# wah.net
KiCad netlist of a schematic drawn in Altium Designer
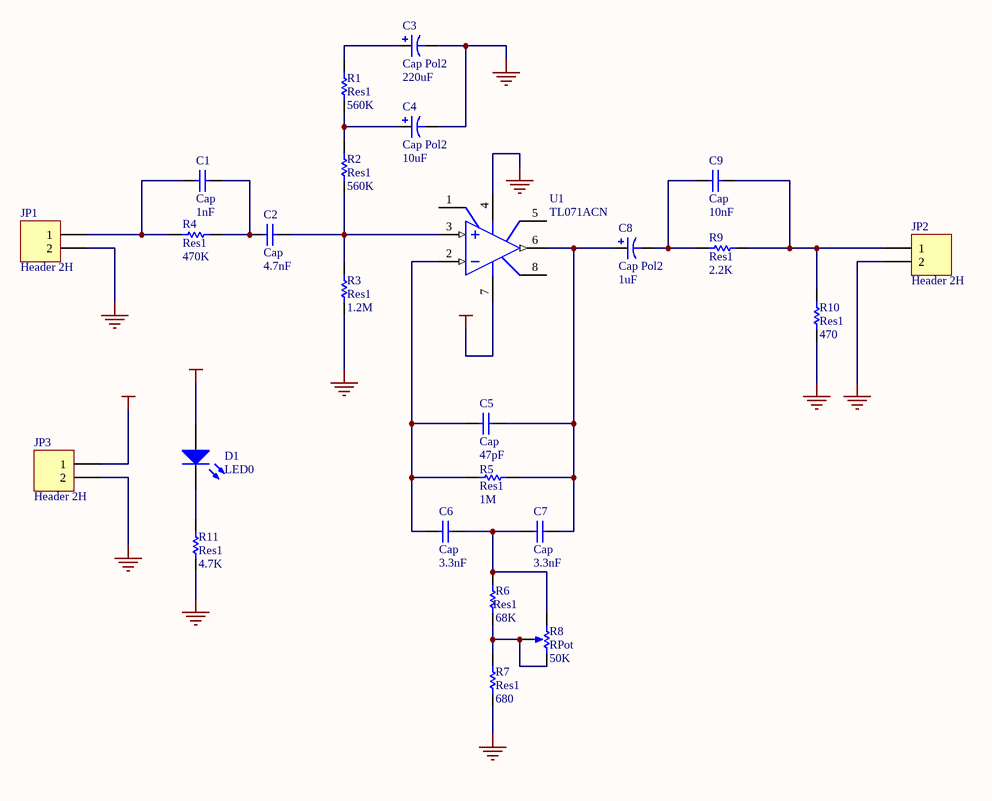
[diagram p0: wah.SCHDOC]

(export (version "E")
  (design (tool "Eeschema 10.0.6"))
  (components
    (comp (ref "C1")
      (value "Cap")
      (footprint "CAPR2.54-5.1X3.2")
      (description "Capacitor")
      (fields (field (name "ALTIUM_VALUE") "1nF") (field (name "PUBLISHER") "Altium Limited"))
      (libsource (lib "Miscellaneous Devices") (part "Cap"))
    )
    (comp (ref "C2")
      (value "Cap")
      (footprint "CAPR2.54-5.1X3.2")
      (description "Capacitor")
      (fields (field (name "ALTIUM_VALUE") "4.7nF") (field (name "PUBLISHER") "Altium Limited"))
      (libsource (lib "Miscellaneous Devices") (part "Cap"))
    )
    (comp (ref "C3")
      (value "Cap Pol2")
      (footprint "CAPPR2-5X6.8")
      (description "Polarized Capacitor (Axial)")
      (fields (field (name "ALTIUM_VALUE") "220uF") (field (name "PUBLISHER") "Altium Limited"))
      (libsource (lib "Miscellaneous Devices") (part "Cap Pol2"))
    )
    (comp (ref "C4")
      (value "Cap Pol2")
      (footprint "CAPPR2-5X6.8")
      (description "Polarized Capacitor (Axial)")
      (fields (field (name "ALTIUM_VALUE") "10uF") (field (name "PUBLISHER") "Altium Limited"))
      (libsource (lib "Miscellaneous Devices") (part "Cap Pol2"))
    )
    (comp (ref "C5")
      (value "Cap")
      (footprint "CAPR2.54-5.1X3.2")
      (description "Capacitor")
      (fields (field (name "ALTIUM_VALUE") "47pF") (field (name "PUBLISHER") "Altium Limited"))
      (libsource (lib "Miscellaneous Devices") (part "Cap"))
    )
    (comp (ref "C6")
      (value "Cap")
      (footprint "CAPR2.54-5.1X3.2")
      (description "Capacitor")
      (fields (field (name "ALTIUM_VALUE") "3.3nF") (field (name "PUBLISHER") "Altium Limited"))
      (libsource (lib "Miscellaneous Devices") (part "Cap"))
    )
    (comp (ref "C7")
      (value "Cap")
      (footprint "CAPR2.54-5.1X3.2")
      (description "Capacitor")
      (fields (field (name "ALTIUM_VALUE") "3.3nF") (field (name "PUBLISHER") "Altium Limited"))
      (libsource (lib "Miscellaneous Devices") (part "Cap"))
    )
    (comp (ref "C8")
      (value "Cap Pol2")
      (footprint "CAPPR2-5X6.8")
      (description "Polarized Capacitor (Axial)")
      (fields (field (name "ALTIUM_VALUE") "1uF") (field (name "PUBLISHER") "Altium Limited"))
      (libsource (lib "Miscellaneous Devices") (part "Cap Pol2"))
    )
    (comp (ref "C9")
      (value "Cap")
      (footprint "CAPR2.54-5.1X3.2")
      (description "Capacitor")
      (fields (field (name "ALTIUM_VALUE") "10nF") (field (name "PUBLISHER") "Altium Limited"))
      (libsource (lib "Miscellaneous Devices") (part "Cap"))
    )
    (comp (ref "D1")
      (value "LED0")
      (footprint "BAT-2")
      (description "Typical INFRARED GaAs LED")
      (fields (field (name "PUBLISHER") "Altium Limited"))
      (libsource (lib "Miscellaneous Devices") (part "LED0"))
    )
    (comp (ref "JP1")
      (value "Header 2H")
      (footprint "HDR1X2")
      (description "Header, 2-Pin, Right Angle")
      (fields (field (name "PUBLISHER") "Altium Limited"))
      (libsource (lib "") (part "Header 2H_1"))
    )
    (comp (ref "JP2")
      (value "Header 2H")
      (footprint "HDR1X2")
      (description "Header, 2-Pin, Right Angle")
      (fields (field (name "PUBLISHER") "Altium Limited"))
      (libsource (lib "Miscellaneous Connectors") (part "Header 2H"))
    )
    (comp (ref "JP3")
      (value "Header 2H")
      (footprint "HDR1X2")
      (description "Header, 2-Pin, Right Angle")
      (fields (field (name "PUBLISHER") "Altium Limited"))
      (libsource (lib "") (part "Header 2H_1"))
    )
    (comp (ref "R1")
      (value "Res1")
      (footprint "AXIAL-0.3")
      (description "Resistor")
      (fields (field (name "ALTIUM_VALUE") "560K") (field (name "PUBLISHER") "Altium Limited"))
      (libsource (lib "Miscellaneous Devices") (part "Res1"))
    )
    (comp (ref "R2")
      (value "Res1")
      (footprint "AXIAL-0.3")
      (description "Resistor")
      (fields (field (name "ALTIUM_VALUE") "560K") (field (name "PUBLISHER") "Altium Limited"))
      (libsource (lib "Miscellaneous Devices") (part "Res1"))
    )
    (comp (ref "R3")
      (value "Res1")
      (footprint "AXIAL-0.3")
      (description "Resistor")
      (fields (field (name "ALTIUM_VALUE") "1.2M") (field (name "PUBLISHER") "Altium Limited"))
      (libsource (lib "Miscellaneous Devices") (part "Res1"))
    )
    (comp (ref "R4")
      (value "Res1")
      (footprint "AXIAL-0.3")
      (description "Resistor")
      (fields (field (name "ALTIUM_VALUE") "470K") (field (name "PUBLISHER") "Altium Limited"))
      (libsource (lib "Miscellaneous Devices") (part "Res1"))
    )
    (comp (ref "R5")
      (value "Res1")
      (footprint "AXIAL-0.3")
      (description "Resistor")
      (fields (field (name "ALTIUM_VALUE") "1M") (field (name "PUBLISHER") "Altium Limited"))
      (libsource (lib "Miscellaneous Devices") (part "Res1"))
    )
    (comp (ref "R6")
      (value "Res1")
      (footprint "AXIAL-0.3")
      (description "Resistor")
      (fields (field (name "ALTIUM_VALUE") "68K") (field (name "PUBLISHER") "Altium Limited"))
      (libsource (lib "Miscellaneous Devices") (part "Res1"))
    )
    (comp (ref "R7")
      (value "Res1")
      (footprint "AXIAL-0.3")
      (description "Resistor")
      (fields (field (name "ALTIUM_VALUE") "680") (field (name "PUBLISHER") "Altium Limited"))
      (libsource (lib "Miscellaneous Devices") (part "Res1"))
    )
    (comp (ref "R8")
      (value "RPot")
      (footprint "VR5")
      (description "Potentiometer")
      (fields (field (name "ALTIUM_VALUE") "50K") (field (name "PUBLISHER") "Altium Limited"))
      (libsource (lib "Miscellaneous Devices") (part "RPot"))
    )
    (comp (ref "R9")
      (value "Res1")
      (footprint "AXIAL-0.3")
      (description "Resistor")
      (fields (field (name "ALTIUM_VALUE") "2.2K") (field (name "PUBLISHER") "Altium Limited"))
      (libsource (lib "Miscellaneous Devices") (part "Res1"))
    )
    (comp (ref "R10")
      (value "Res1")
      (footprint "AXIAL-0.3")
      (description "Resistor")
      (fields (field (name "ALTIUM_VALUE") "470") (field (name "PUBLISHER") "Altium Limited"))
      (libsource (lib "Miscellaneous Devices") (part "Res1"))
    )
    (comp (ref "R11")
      (value "Res1")
      (footprint "AXIAL-0.3")
      (description "Resistor")
      (fields (field (name "ALTIUM_VALUE") "4.7K") (field (name "PUBLISHER") "Altium Limited"))
      (libsource (lib "Miscellaneous Devices") (part "Res1"))
    )
    (comp (ref "U1")
      (value "TL071ACN")
      (footprint "DIP8")
      (description "Low-Noise J-FET Single Operational Amplifier")
      (fields (field (name "PUBLISHER") "Altium Limited"))
      (libsource (lib "ST Operational Amplifier") (part "TL071ACN"))
    )
  )
  (nets
    (net (code "1") (name "GND") (class "Default")
      (node (ref "C3") (pin "2") (pinfunction "2_2") (pintype "passive"))
      (node (ref "C4") (pin "2") (pinfunction "2_2") (pintype "passive"))
      (node (ref "JP1") (pin "2") (pinfunction "2_2") (pintype "passive"))
      (node (ref "JP2") (pin "2") (pinfunction "2_2") (pintype "passive"))
      (node (ref "JP3") (pin "2") (pinfunction "2_2") (pintype "passive"))
      (node (ref "R10") (pin "1") (pinfunction "1_1") (pintype "passive"))
      (node (ref "R11") (pin "1") (pinfunction "1_1") (pintype "passive"))
      (node (ref "R3") (pin "1") (pinfunction "1_1") (pintype "passive"))
      (node (ref "R7") (pin "1") (pinfunction "1_1") (pintype "passive"))
      (node (ref "U1") (pin "4") (pinfunction "V-_4") (pintype "power_in"))
    )
    (net (code "2") (name "Net-(C1-Pad1)") (class "Default")
      (node (ref "C1") (pin "1") (pinfunction "1_1") (pintype "passive"))
      (node (ref "JP1") (pin "1") (pinfunction "1_1") (pintype "passive"))
      (node (ref "R4") (pin "1") (pinfunction "1_1") (pintype "passive"))
    )
    (net (code "3") (name "Net-(C1-Pad2)") (class "Default")
      (node (ref "C1") (pin "2") (pinfunction "2_2") (pintype "passive"))
      (node (ref "C2") (pin "1") (pinfunction "1_1") (pintype "passive"))
      (node (ref "R4") (pin "2") (pinfunction "2_2") (pintype "passive"))
    )
    (net (code "4") (name "Net-(C3-Pad1)") (class "Default")
      (node (ref "C3") (pin "1") (pinfunction "1_1") (pintype "passive"))
      (node (ref "R1") (pin "2") (pinfunction "2_2") (pintype "passive"))
    )
    (net (code "5") (name "Net-(C4-Pad1)") (class "Default")
      (node (ref "C4") (pin "1") (pinfunction "1_1") (pintype "passive"))
      (node (ref "R1") (pin "1") (pinfunction "1_1") (pintype "passive"))
      (node (ref "R2") (pin "2") (pinfunction "2_2") (pintype "passive"))
    )
    (net (code "6") (name "Net-(C8-Pad2)") (class "Default")
      (node (ref "C8") (pin "2") (pinfunction "2_2") (pintype "passive"))
      (node (ref "C9") (pin "1") (pinfunction "1_1") (pintype "passive"))
      (node (ref "R9") (pin "2") (pinfunction "2_2") (pintype "passive"))
    )
    (net (code "7") (name "Net-(C9-Pad2)") (class "Default")
      (node (ref "C9") (pin "2") (pinfunction "2_2") (pintype "passive"))
      (node (ref "JP2") (pin "1") (pinfunction "1_1") (pintype "passive"))
      (node (ref "R10") (pin "2") (pinfunction "2_2") (pintype "passive"))
      (node (ref "R9") (pin "1") (pinfunction "1_1") (pintype "passive"))
    )
    (net (code "8") (name "Net-(D1-K)") (class "Default")
      (node (ref "D1") (pin "2") (pinfunction "K_2") (pintype "passive"))
      (node (ref "R11") (pin "2") (pinfunction "2_2") (pintype "passive"))
    )
    (net (code "9") (name "Net-(R8-BOT)") (class "Default")
      (node (ref "R6") (pin "1") (pinfunction "1_1") (pintype "passive"))
      (node (ref "R7") (pin "2") (pinfunction "2_2") (pintype "passive"))
      (node (ref "R8") (pin "2") (pinfunction "BOT_2") (pintype "passive"))
      (node (ref "R8") (pin "3") (pinfunction "TAP_3") (pintype "passive"))
    )
    (net (code "10") (name "Net-(R8-TOP)") (class "Default")
      (node (ref "C6") (pin "2") (pinfunction "2_2") (pintype "passive"))
      (node (ref "C7") (pin "1") (pinfunction "1_1") (pintype "passive"))
      (node (ref "R6") (pin "2") (pinfunction "2_2") (pintype "passive"))
      (node (ref "R8") (pin "1") (pinfunction "TOP_1") (pintype "passive"))
    )
    (net (code "11") (name "Net-(U1-IN+)") (class "Default")
      (node (ref "C2") (pin "2") (pinfunction "2_2") (pintype "passive"))
      (node (ref "R2") (pin "1") (pinfunction "1_1") (pintype "passive"))
      (node (ref "R3") (pin "2") (pinfunction "2_2") (pintype "passive"))
      (node (ref "U1") (pin "3") (pinfunction "IN+_3") (pintype "input"))
    )
    (net (code "12") (name "Net-(U1-IN-)") (class "Default")
      (node (ref "C5") (pin "1") (pinfunction "1_1") (pintype "passive"))
      (node (ref "C6") (pin "1") (pinfunction "1_1") (pintype "passive"))
      (node (ref "R5") (pin "1") (pinfunction "1_1") (pintype "passive"))
      (node (ref "U1") (pin "2") (pinfunction "IN-_2") (pintype "input"))
    )
    (net (code "13") (name "Net-(U1-OUT)") (class "Default")
      (node (ref "C5") (pin "2") (pinfunction "2_2") (pintype "passive"))
      (node (ref "C7") (pin "2") (pinfunction "2_2") (pintype "passive"))
      (node (ref "C8") (pin "1") (pinfunction "1_1") (pintype "passive"))
      (node (ref "R5") (pin "2") (pinfunction "2_2") (pintype "passive"))
      (node (ref "U1") (pin "6") (pinfunction "OUT_6") (pintype "output"))
    )
    (net (code "14") (name "VCC") (class "Default")
      (node (ref "D1") (pin "1") (pinfunction "A_1") (pintype "passive"))
      (node (ref "JP3") (pin "1") (pinfunction "1_1") (pintype "passive"))
      (node (ref "U1") (pin "7") (pinfunction "V+_7") (pintype "power_in"))
    )
    (net (code "15") (name "unconnected-(U1-NC-Pad8)") (class "Default")
      (node (ref "U1") (pin "8") (pinfunction "NC_8") (pintype "passive"))
    )
    (net (code "16") (name "unconnected-(U1-OS_NULL-Pad1)") (class "Default")
      (node (ref "U1") (pin "1") (pinfunction "OS_NULL_1") (pintype "passive"))
    )
    (net (code "17") (name "unconnected-(U1-OS_NULL-Pad5)") (class "Default")
      (node (ref "U1") (pin "5") (pinfunction "OS_NULL_5") (pintype "passive"))
    )
  )
)
